# MainBoard.net
KiCad netlist of a schematic drawn in EAGLE
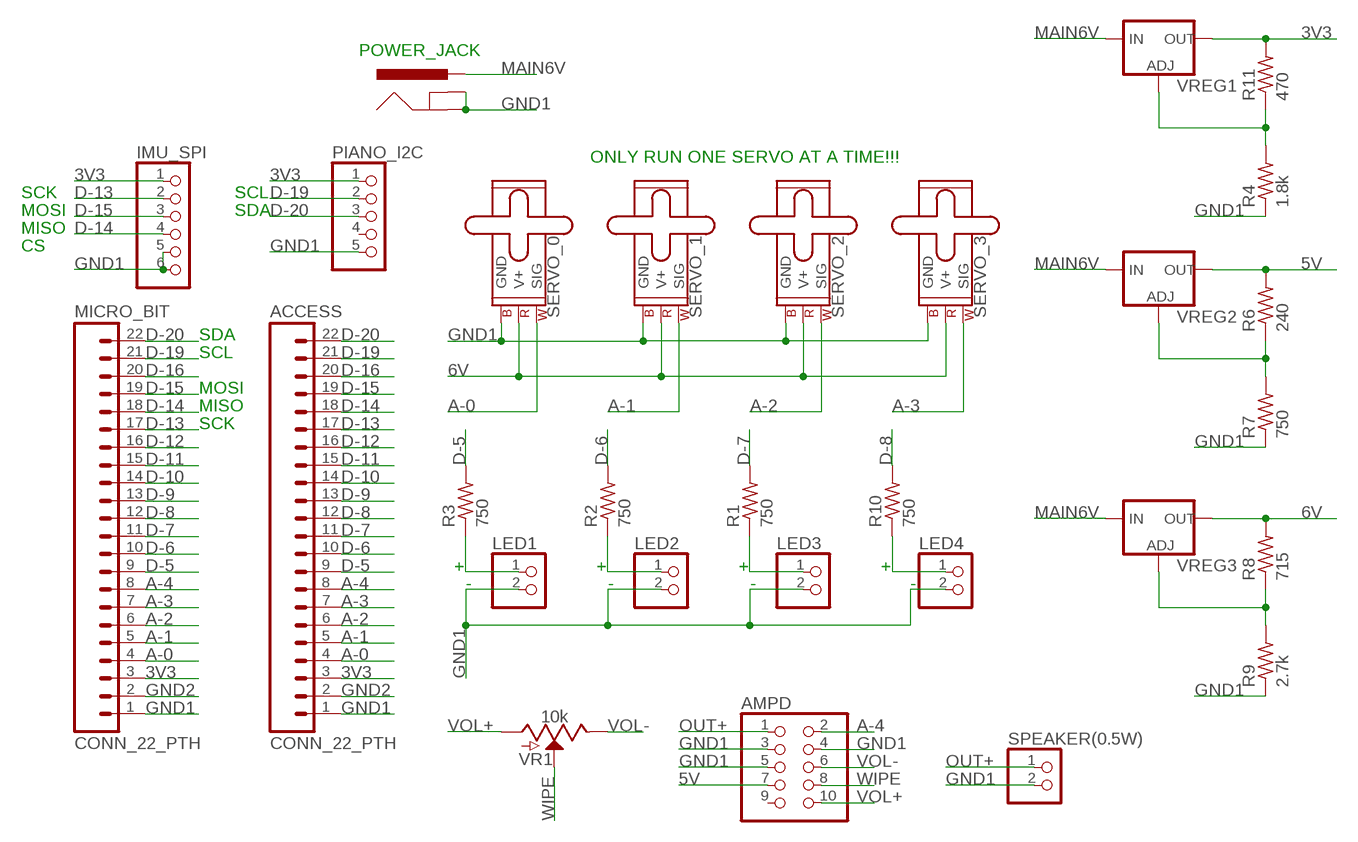
[diagram p0: schematic, sheet 1]

(export (version "E")
  (design (tool "Eeschema 10.0.6"))
  (components
    (comp (ref "ACCESS")
      (value "CONN_22_PTH")
      (footprint "eagle-import:1X22")
      (libsource (lib "eagle-import") (part "CONN_22_PTH"))
    )
    (comp (ref "AMPD")
      (value "PINHD-2X5")
      (footprint "eagle-import:2X05")
      (libsource (lib "eagle-import") (part "PINHD-2X5"))
    )
    (comp (ref "IMU_SPI")
      (value "PINHD-1X6")
      (footprint "eagle-import:1X06")
      (libsource (lib "eagle-import") (part "PINHD-1X6"))
    )
    (comp (ref "LED1")
      (value "PINHD-1X2")
      (footprint "eagle-import:1X02")
      (libsource (lib "eagle-import") (part "PINHD-1X2"))
    )
    (comp (ref "LED2")
      (value "PINHD-1X2")
      (footprint "eagle-import:1X02")
      (libsource (lib "eagle-import") (part "PINHD-1X2"))
    )
    (comp (ref "LED3")
      (value "PINHD-1X2")
      (footprint "eagle-import:1X02")
      (libsource (lib "eagle-import") (part "PINHD-1X2"))
    )
    (comp (ref "LED4")
      (value "PINHD-1X2")
      (footprint "eagle-import:1X02")
      (libsource (lib "eagle-import") (part "PINHD-1X2"))
    )
    (comp (ref "MICRO_BIT")
      (value "CONN_22_PTH")
      (footprint "eagle-import:1X22")
      (libsource (lib "eagle-import") (part "CONN_22_PTH"))
    )
    (comp (ref "PIANO_I2C")
      (value "PINHD-1X5")
      (footprint "eagle-import:1X05")
      (libsource (lib "eagle-import") (part "PINHD-1X5"))
    )
    (comp (ref "POWER_JACK")
      (value "POWER_JACKPTH_BREAD")
      (footprint "eagle-import:POWER_JACK_PTH_BREAD")
      (libsource (lib "eagle-import") (part "POWER_JACKPTH_BREAD"))
    )
    (comp (ref "R1")
      (value "750")
      (footprint "eagle-import:0207_10")
      (libsource (lib "eagle-import") (part "R-US_0207/10"))
    )
    (comp (ref "R2")
      (value "750")
      (footprint "eagle-import:0207_10")
      (libsource (lib "eagle-import") (part "R-US_0207/10"))
    )
    (comp (ref "R3")
      (value "750")
      (footprint "eagle-import:0207_10")
      (libsource (lib "eagle-import") (part "R-US_0207/10"))
    )
    (comp (ref "R4")
      (value "1.8k")
      (footprint "eagle-import:0207_10")
      (libsource (lib "eagle-import") (part "R-US_0207/10"))
    )
    (comp (ref "R6")
      (value "240")
      (footprint "eagle-import:0207_10")
      (libsource (lib "eagle-import") (part "R-US_0207/10"))
    )
    (comp (ref "R7")
      (value "750")
      (footprint "eagle-import:0207_10")
      (libsource (lib "eagle-import") (part "R-US_0207/10"))
    )
    (comp (ref "R8")
      (value "715")
      (footprint "eagle-import:0207_10")
      (libsource (lib "eagle-import") (part "R-US_0207/10"))
    )
    (comp (ref "R9")
      (value "2.7k")
      (footprint "eagle-import:0207_10")
      (libsource (lib "eagle-import") (part "R-US_0207/10"))
    )
    (comp (ref "R10")
      (value "750")
      (footprint "eagle-import:0207_10")
      (libsource (lib "eagle-import") (part "R-US_0207/10"))
    )
    (comp (ref "R11")
      (value "470")
      (footprint "eagle-import:0207_10")
      (libsource (lib "eagle-import") (part "R-US_0207/10"))
    )
    (comp (ref "SERVO_0")
      (value "SERVO")
      (footprint "eagle-import:1X03")
      (libsource (lib "eagle-import") (part "SERVO"))
    )
    (comp (ref "SERVO_1")
      (value "SERVO")
      (footprint "eagle-import:1X03")
      (libsource (lib "eagle-import") (part "SERVO"))
    )
    (comp (ref "SERVO_2")
      (value "SERVO")
      (footprint "eagle-import:1X03")
      (libsource (lib "eagle-import") (part "SERVO"))
    )
    (comp (ref "SERVO_3")
      (value "SERVO")
      (footprint "eagle-import:1X03")
      (libsource (lib "eagle-import") (part "SERVO"))
    )
    (comp (ref "SPEAKER(0.5W)")
      (value "PINHD-1X2")
      (footprint "eagle-import:1X02")
      (libsource (lib "eagle-import") (part "PINHD-1X2"))
    )
    (comp (ref "VR1")
      (value "10k")
      (footprint "eagle-import:POT-PTH-ALPS")
      (libsource (lib "eagle-import") (part "POTENTIOMETER-PTH-9MM-1/20W-20%"))
    )
    (comp (ref "VREG1")
      (value "V_REG_317SINK")
      (footprint "eagle-import:TO220-ADJ")
      (libsource (lib "eagle-import") (part "V_REG_317SINK"))
    )
    (comp (ref "VREG2")
      (value "V_REG_317SINK")
      (footprint "eagle-import:TO220-ADJ")
      (libsource (lib "eagle-import") (part "V_REG_317SINK"))
    )
    (comp (ref "VREG3")
      (value "V_REG_317SINK")
      (footprint "eagle-import:TO220-ADJ")
      (libsource (lib "eagle-import") (part "V_REG_317SINK"))
    )
  )
  (nets
    (net (code "1") (name "/3V3") (class "Default")
      (node (ref "ACCESS") (pin "3") (pinfunction "3_3") (pintype "passive"))
      (node (ref "IMU_SPI") (pin "1") (pinfunction "1_1") (pintype "passive"))
      (node (ref "MICRO_BIT") (pin "3") (pinfunction "3_3") (pintype "passive"))
      (node (ref "PIANO_I2C") (pin "1") (pinfunction "1_1") (pintype "passive"))
      (node (ref "R11") (pin "2") (pinfunction "2_2") (pintype "passive"))
      (node (ref "VREG1") (pin "OUT") (pinfunction "OUT_OUT") (pintype "output"))
    )
    (net (code "2") (name "/5V") (class "Default")
      (node (ref "AMPD") (pin "7") (pinfunction "7_7") (pintype "passive"))
      (node (ref "R6") (pin "2") (pinfunction "2_2") (pintype "passive"))
      (node (ref "VREG2") (pin "OUT") (pinfunction "OUT_OUT") (pintype "output"))
    )
    (net (code "3") (name "/6V") (class "Default")
      (node (ref "R8") (pin "2") (pinfunction "2_2") (pintype "passive"))
      (node (ref "SERVO_0") (pin "2") (pinfunction "V+_2") (pintype "bidirectional"))
      (node (ref "SERVO_1") (pin "2") (pinfunction "V+_2") (pintype "bidirectional"))
      (node (ref "SERVO_2") (pin "2") (pinfunction "V+_2") (pintype "bidirectional"))
      (node (ref "SERVO_3") (pin "2") (pinfunction "V+_2") (pintype "bidirectional"))
      (node (ref "VREG3") (pin "OUT") (pinfunction "OUT_OUT") (pintype "output"))
    )
    (net (code "4") (name "/A-0") (class "Default")
      (node (ref "ACCESS") (pin "4") (pinfunction "4_4") (pintype "passive"))
      (node (ref "MICRO_BIT") (pin "4") (pinfunction "4_4") (pintype "passive"))
      (node (ref "SERVO_0") (pin "1") (pinfunction "SIG_1") (pintype "bidirectional"))
    )
    (net (code "5") (name "/A-1") (class "Default")
      (node (ref "ACCESS") (pin "5") (pinfunction "5_5") (pintype "passive"))
      (node (ref "MICRO_BIT") (pin "5") (pinfunction "5_5") (pintype "passive"))
      (node (ref "SERVO_1") (pin "1") (pinfunction "SIG_1") (pintype "bidirectional"))
    )
    (net (code "6") (name "/A-2") (class "Default")
      (node (ref "ACCESS") (pin "6") (pinfunction "6_6") (pintype "passive"))
      (node (ref "MICRO_BIT") (pin "6") (pinfunction "6_6") (pintype "passive"))
      (node (ref "SERVO_2") (pin "1") (pinfunction "SIG_1") (pintype "bidirectional"))
    )
    (net (code "7") (name "/A-3") (class "Default")
      (node (ref "ACCESS") (pin "7") (pinfunction "7_7") (pintype "passive"))
      (node (ref "MICRO_BIT") (pin "7") (pinfunction "7_7") (pintype "passive"))
      (node (ref "SERVO_3") (pin "1") (pinfunction "SIG_1") (pintype "bidirectional"))
    )
    (net (code "8") (name "/A-4") (class "Default")
      (node (ref "ACCESS") (pin "8") (pinfunction "8_8") (pintype "passive"))
      (node (ref "AMPD") (pin "2") (pinfunction "2_2") (pintype "passive"))
      (node (ref "MICRO_BIT") (pin "8") (pinfunction "8_8") (pintype "passive"))
    )
    (net (code "9") (name "/D-5") (class "Default")
      (node (ref "ACCESS") (pin "9") (pinfunction "9_9") (pintype "passive"))
      (node (ref "MICRO_BIT") (pin "9") (pinfunction "9_9") (pintype "passive"))
      (node (ref "R3") (pin "2") (pinfunction "2_2") (pintype "passive"))
    )
    (net (code "10") (name "/D-6") (class "Default")
      (node (ref "ACCESS") (pin "10") (pinfunction "10_10") (pintype "passive"))
      (node (ref "MICRO_BIT") (pin "10") (pinfunction "10_10") (pintype "passive"))
      (node (ref "R2") (pin "2") (pinfunction "2_2") (pintype "passive"))
    )
    (net (code "11") (name "/D-7") (class "Default")
      (node (ref "ACCESS") (pin "11") (pinfunction "11_11") (pintype "passive"))
      (node (ref "MICRO_BIT") (pin "11") (pinfunction "11_11") (pintype "passive"))
      (node (ref "R1") (pin "2") (pinfunction "2_2") (pintype "passive"))
    )
    (net (code "12") (name "/D-8") (class "Default")
      (node (ref "ACCESS") (pin "12") (pinfunction "12_12") (pintype "passive"))
      (node (ref "MICRO_BIT") (pin "12") (pinfunction "12_12") (pintype "passive"))
      (node (ref "R10") (pin "2") (pinfunction "2_2") (pintype "passive"))
    )
    (net (code "13") (name "/D-9") (class "Default")
      (node (ref "ACCESS") (pin "13") (pinfunction "13_13") (pintype "passive"))
      (node (ref "MICRO_BIT") (pin "13") (pinfunction "13_13") (pintype "passive"))
    )
    (net (code "14") (name "/D-10") (class "Default")
      (node (ref "ACCESS") (pin "14") (pinfunction "14_14") (pintype "passive"))
      (node (ref "MICRO_BIT") (pin "14") (pinfunction "14_14") (pintype "passive"))
    )
    (net (code "15") (name "/D-11") (class "Default")
      (node (ref "ACCESS") (pin "15") (pinfunction "15_15") (pintype "passive"))
      (node (ref "MICRO_BIT") (pin "15") (pinfunction "15_15") (pintype "passive"))
    )
    (net (code "16") (name "/D-12") (class "Default")
      (node (ref "ACCESS") (pin "16") (pinfunction "16_16") (pintype "passive"))
      (node (ref "MICRO_BIT") (pin "16") (pinfunction "16_16") (pintype "passive"))
    )
    (net (code "17") (name "/D-13") (class "Default")
      (node (ref "ACCESS") (pin "17") (pinfunction "17_17") (pintype "passive"))
      (node (ref "IMU_SPI") (pin "2") (pinfunction "2_2") (pintype "passive"))
      (node (ref "MICRO_BIT") (pin "17") (pinfunction "17_17") (pintype "passive"))
    )
    (net (code "18") (name "/D-14") (class "Default")
      (node (ref "ACCESS") (pin "18") (pinfunction "18_18") (pintype "passive"))
      (node (ref "IMU_SPI") (pin "4") (pinfunction "4_4") (pintype "passive"))
      (node (ref "MICRO_BIT") (pin "18") (pinfunction "18_18") (pintype "passive"))
    )
    (net (code "19") (name "/D-15") (class "Default")
      (node (ref "ACCESS") (pin "19") (pinfunction "19_19") (pintype "passive"))
      (node (ref "IMU_SPI") (pin "3") (pinfunction "3_3") (pintype "passive"))
      (node (ref "MICRO_BIT") (pin "19") (pinfunction "19_19") (pintype "passive"))
    )
    (net (code "20") (name "/D-16") (class "Default")
      (node (ref "ACCESS") (pin "20") (pinfunction "20_20") (pintype "passive"))
      (node (ref "MICRO_BIT") (pin "20") (pinfunction "20_20") (pintype "passive"))
    )
    (net (code "21") (name "/D-19") (class "Default")
      (node (ref "ACCESS") (pin "21") (pinfunction "21_21") (pintype "passive"))
      (node (ref "MICRO_BIT") (pin "21") (pinfunction "21_21") (pintype "passive"))
      (node (ref "PIANO_I2C") (pin "2") (pinfunction "2_2") (pintype "passive"))
    )
    (net (code "22") (name "/D-20") (class "Default")
      (node (ref "ACCESS") (pin "22") (pinfunction "22_22") (pintype "passive"))
      (node (ref "MICRO_BIT") (pin "22") (pinfunction "22_22") (pintype "passive"))
      (node (ref "PIANO_I2C") (pin "3") (pinfunction "3_3") (pintype "passive"))
    )
    (net (code "23") (name "/GND1") (class "Default")
      (node (ref "ACCESS") (pin "1") (pinfunction "1_1") (pintype "passive"))
      (node (ref "AMPD") (pin "3") (pinfunction "3_3") (pintype "passive"))
      (node (ref "AMPD") (pin "4") (pinfunction "4_4") (pintype "passive"))
      (node (ref "AMPD") (pin "5") (pinfunction "5_5") (pintype "passive"))
      (node (ref "IMU_SPI") (pin "5") (pinfunction "5_5") (pintype "passive"))
      (node (ref "IMU_SPI") (pin "6") (pinfunction "6_6") (pintype "passive"))
      (node (ref "LED1") (pin "2") (pinfunction "2_2") (pintype "passive"))
      (node (ref "LED2") (pin "2") (pinfunction "2_2") (pintype "passive"))
      (node (ref "LED3") (pin "2") (pinfunction "2_2") (pintype "passive"))
      (node (ref "LED4") (pin "2") (pinfunction "2_2") (pintype "passive"))
      (node (ref "MICRO_BIT") (pin "1") (pinfunction "1_1") (pintype "passive"))
      (node (ref "PIANO_I2C") (pin "5") (pinfunction "5_5") (pintype "passive"))
      (node (ref "POWER_JACK") (pin "GND") (pinfunction "GND_GND") (pintype "bidirectional"))
      (node (ref "POWER_JACK") (pin "GNDBREAK") (pinfunction "GNDBREAK_GNDBREAK") (pintype "bidirectional"))
      (node (ref "R4") (pin "1") (pinfunction "1_1") (pintype "passive"))
      (node (ref "R7") (pin "1") (pinfunction "1_1") (pintype "passive"))
      (node (ref "R9") (pin "1") (pinfunction "1_1") (pintype "passive"))
      (node (ref "SERVO_0") (pin "3") (pinfunction "GND_3") (pintype "bidirectional"))
      (node (ref "SERVO_1") (pin "3") (pinfunction "GND_3") (pintype "bidirectional"))
      (node (ref "SERVO_2") (pin "3") (pinfunction "GND_3") (pintype "bidirectional"))
      (node (ref "SERVO_3") (pin "3") (pinfunction "GND_3") (pintype "bidirectional"))
      (node (ref "SPEAKER(0.5W)") (pin "2") (pinfunction "2_2") (pintype "passive"))
    )
    (net (code "24") (name "/GND2") (class "Default")
      (node (ref "ACCESS") (pin "2") (pinfunction "2_2") (pintype "passive"))
      (node (ref "MICRO_BIT") (pin "2") (pinfunction "2_2") (pintype "passive"))
    )
    (net (code "25") (name "/MAIN6V") (class "Default")
      (node (ref "POWER_JACK") (pin "PWR") (pinfunction "PWR_PWR") (pintype "bidirectional"))
      (node (ref "VREG1") (pin "IN") (pinfunction "IN_IN") (pintype "input"))
      (node (ref "VREG2") (pin "IN") (pinfunction "IN_IN") (pintype "input"))
      (node (ref "VREG3") (pin "IN") (pinfunction "IN_IN") (pintype "input"))
    )
    (net (code "26") (name "/OUT+") (class "Default")
      (node (ref "AMPD") (pin "1") (pinfunction "1_1") (pintype "passive"))
      (node (ref "SPEAKER(0.5W)") (pin "1") (pinfunction "1_1") (pintype "passive"))
    )
    (net (code "27") (name "/VOL+") (class "Default")
      (node (ref "AMPD") (pin "10") (pinfunction "10_10") (pintype "passive"))
      (node (ref "VR1") (pin "P$3") (pinfunction "A_P$3") (pintype "passive"))
    )
    (net (code "28") (name "/VOL-") (class "Default")
      (node (ref "AMPD") (pin "6") (pinfunction "6_6") (pintype "passive"))
      (node (ref "VR1") (pin "P$1") (pinfunction "E_P$1") (pintype "passive"))
    )
    (net (code "29") (name "/WIPE") (class "Default")
      (node (ref "AMPD") (pin "8") (pinfunction "8_8") (pintype "passive"))
      (node (ref "VR1") (pin "P$2") (pinfunction "S_P$2") (pintype "passive"))
    )
    (net (code "30") (name "Net-(LED1-Pad1)") (class "Default")
      (node (ref "LED1") (pin "1") (pinfunction "1_1") (pintype "passive"))
      (node (ref "R3") (pin "1") (pinfunction "1_1") (pintype "passive"))
    )
    (net (code "31") (name "Net-(LED2-Pad1)") (class "Default")
      (node (ref "LED2") (pin "1") (pinfunction "1_1") (pintype "passive"))
      (node (ref "R2") (pin "1") (pinfunction "1_1") (pintype "passive"))
    )
    (net (code "32") (name "Net-(LED3-Pad1)") (class "Default")
      (node (ref "LED3") (pin "1") (pinfunction "1_1") (pintype "passive"))
      (node (ref "R1") (pin "1") (pinfunction "1_1") (pintype "passive"))
    )
    (net (code "33") (name "Net-(LED4-Pad1)") (class "Default")
      (node (ref "LED4") (pin "1") (pinfunction "1_1") (pintype "passive"))
      (node (ref "R10") (pin "1") (pinfunction "1_1") (pintype "passive"))
    )
    (net (code "34") (name "Net-(R6-Pad1)") (class "Default")
      (node (ref "R6") (pin "1") (pinfunction "1_1") (pintype "passive"))
      (node (ref "R7") (pin "2") (pinfunction "2_2") (pintype "passive"))
      (node (ref "VREG2") (pin "ADJ") (pinfunction "ADJ_ADJ") (pintype "input"))
    )
    (net (code "35") (name "Net-(R8-Pad1)") (class "Default")
      (node (ref "R8") (pin "1") (pinfunction "1_1") (pintype "passive"))
      (node (ref "R9") (pin "2") (pinfunction "2_2") (pintype "passive"))
      (node (ref "VREG3") (pin "ADJ") (pinfunction "ADJ_ADJ") (pintype "input"))
    )
    (net (code "36") (name "Net-(R11-Pad1)") (class "Default")
      (node (ref "R11") (pin "1") (pinfunction "1_1") (pintype "passive"))
      (node (ref "R4") (pin "2") (pinfunction "2_2") (pintype "passive"))
      (node (ref "VREG1") (pin "ADJ") (pinfunction "ADJ_ADJ") (pintype "input"))
    )
    (net (code "37") (name "unconnected-(AMPD-Pad9)") (class "Default")
      (node (ref "AMPD") (pin "9") (pinfunction "9_9") (pintype "passive"))
    )
    (net (code "38") (name "unconnected-(PIANO_I2C-Pad4)") (class "Default")
      (node (ref "PIANO_I2C") (pin "4") (pinfunction "4_4") (pintype "passive"))
    )
  )
)
